# Teensylu-1_1.net
KiCad netlist of a schematic drawn in EAGLE
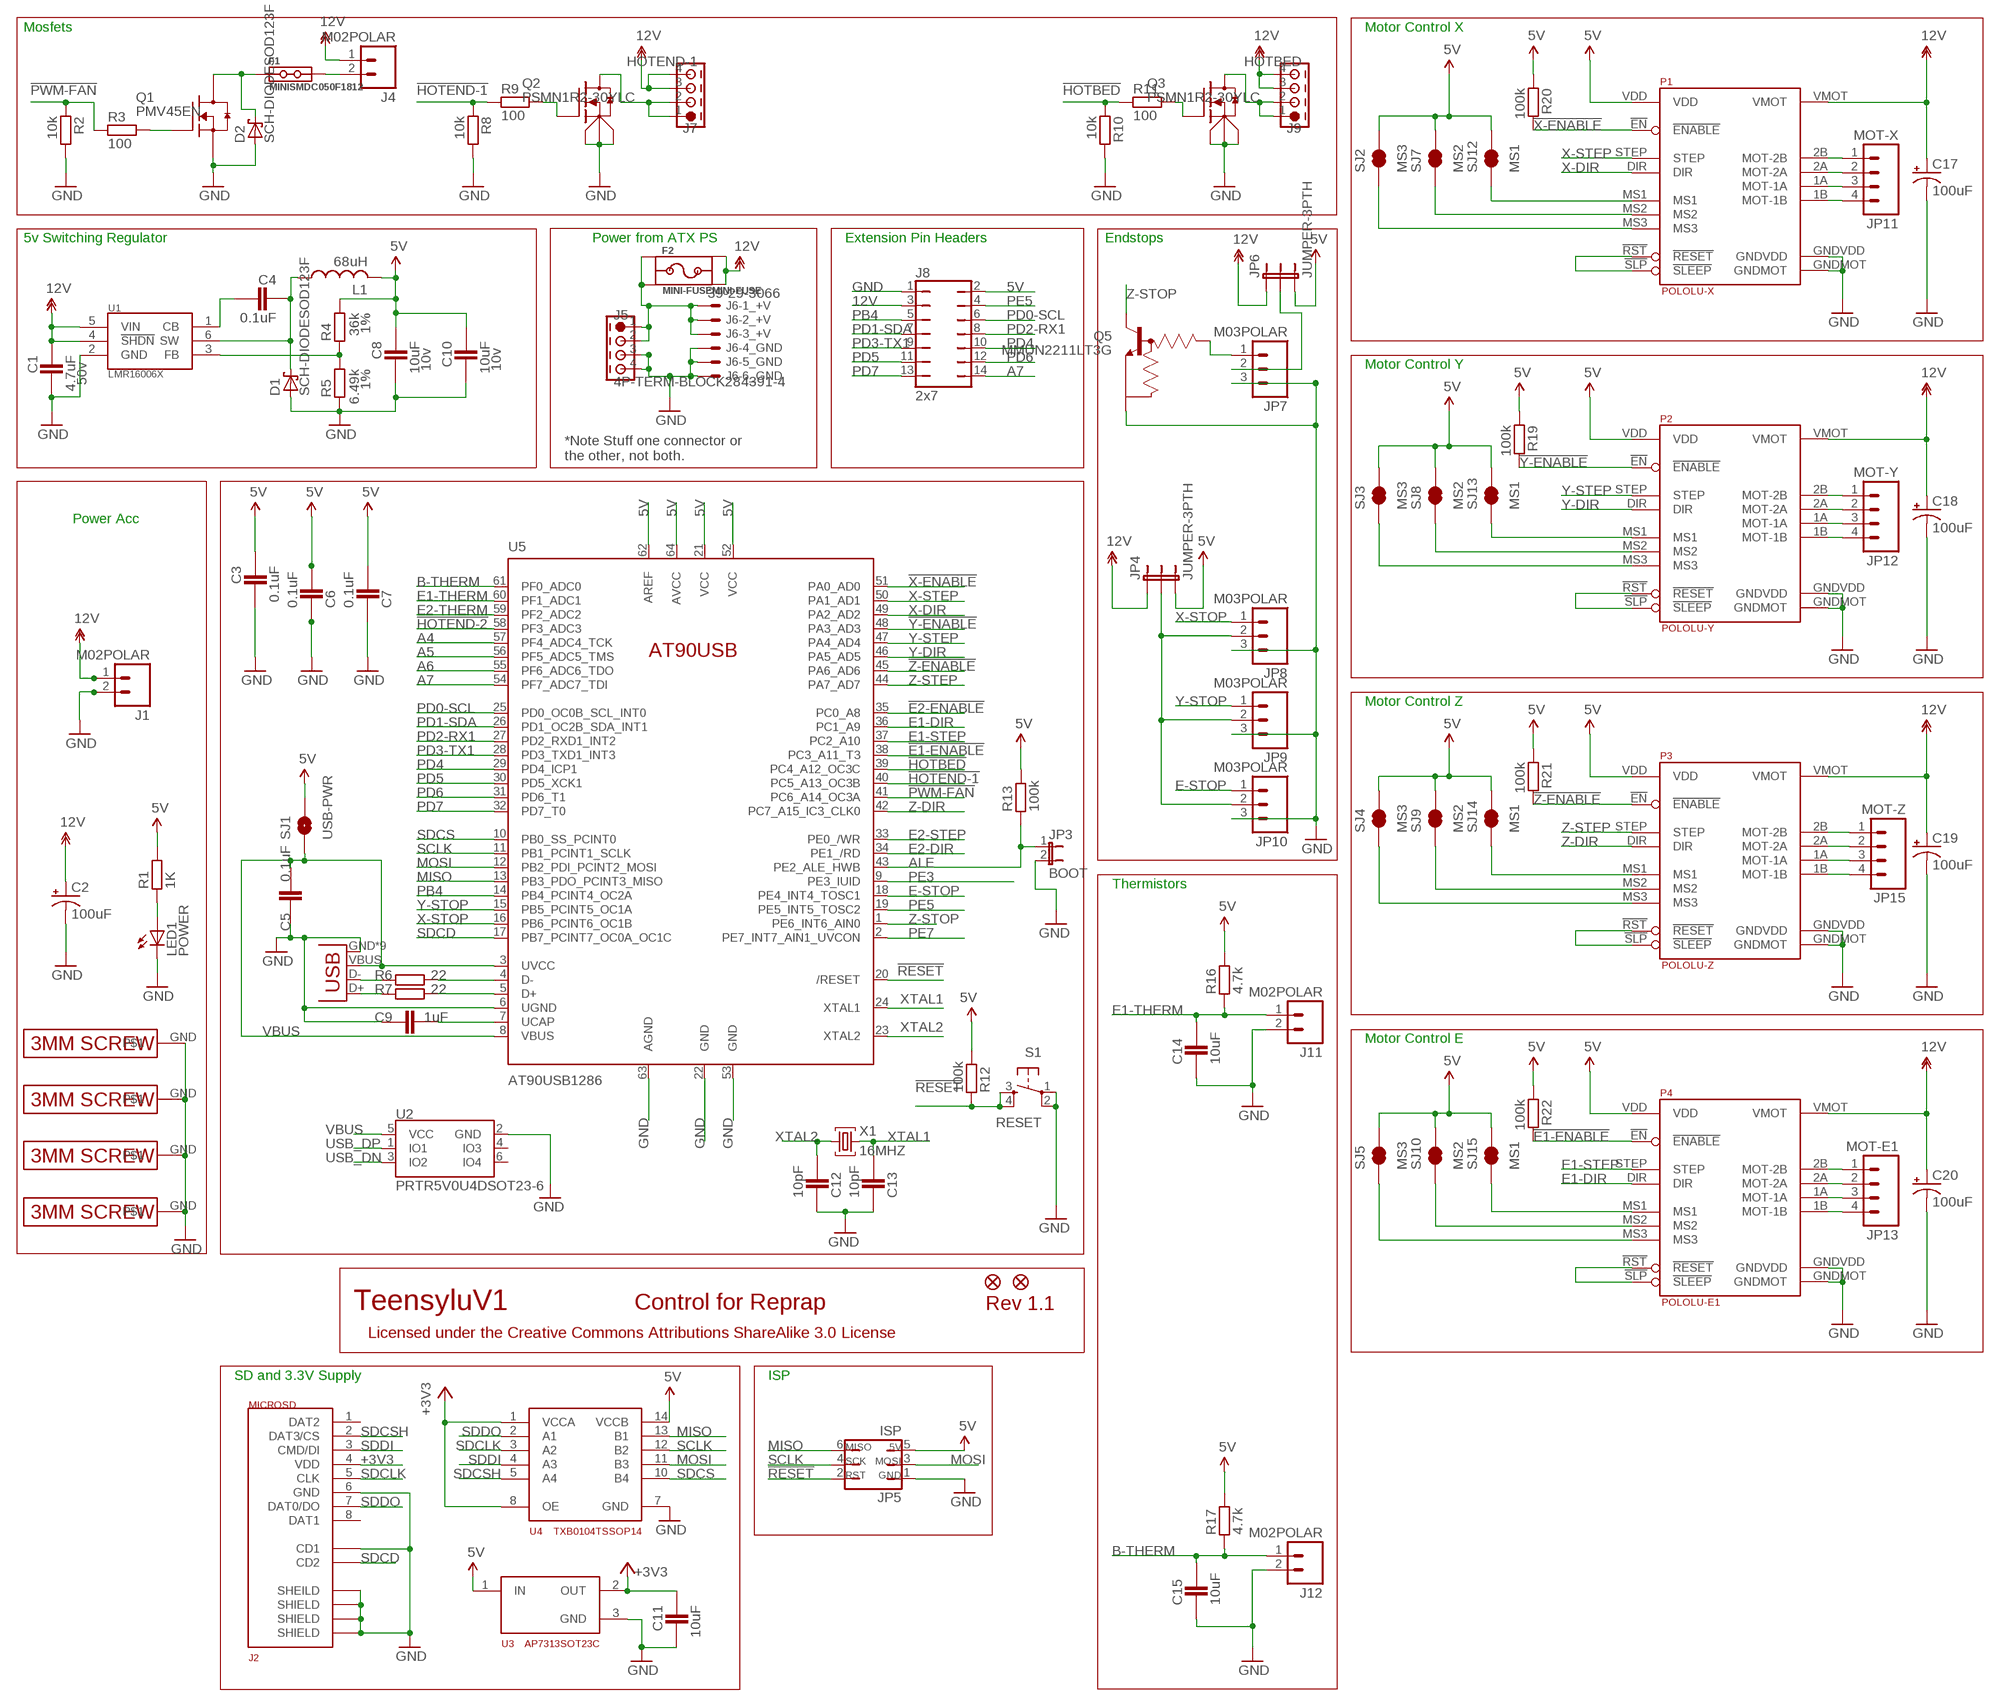
[diagram p0: schematic, sheet 1]

(export (version "E")
  (design (tool "Eeschema 10.0.6"))
  (components
    (comp (ref "C1")
      (value "4.7uF")
      (footprint "eagle-import:CAPC3215X168N")
      (fields
        (field (name "MANUFACTURER") "Yaiyo Yuden")
        (field (name "MANUFACTURER_PART_NUMBER") "UMK316AB7475KL-T")
        (field (name "TOLERANCE") "10%")
        (field (name "VDC") "50v")
      )
      (libsource (lib "eagle-import") (part "CAPACITOR_1206"))
    )
    (comp (ref "C2")
      (value "100uF")
      (footprint "eagle-import:PANASONIC_D")
      (fields
        (field (name "MANUFACTURER") "Panasonic")
        (field (name "MANUFACTURER_PART_NUMBER") "EEE-FTH101XAP")
        (field (name "TOLERANCE") "20%")
      )
      (libsource (lib "eagle-import") (part "CPOL-USD"))
    )
    (comp (ref "C3")
      (value "0.1uF")
      (footprint "eagle-import:CAPC1608X92N")
      (fields
        (field (name "MANUFACTURER") "Murata")
        (field (name "MANUFACTURER_PART_NUMBER") "GRM188R71C104KA01D")
        (field (name "TOLERANCE") "10%")
      )
      (libsource (lib "eagle-import") (part "CAPACITOR_0603"))
    )
    (comp (ref "C4")
      (value "0.1uF")
      (footprint "eagle-import:CAPC1608X92N")
      (fields
        (field (name "MANUFACTURER") "Samsung")
        (field (name "MANUFACTURER_PART_NUMBER") "CL10B104KB8NNNC")
        (field (name "TOLERANCE") "10%")
      )
      (libsource (lib "eagle-import") (part "CAPACITOR_0603"))
    )
    (comp (ref "C5")
      (value "0.1uF")
      (footprint "eagle-import:CAPC1608X92N")
      (fields
        (field (name "MANUFACTURER") "Murata")
        (field (name "MANUFACTURER_PART_NUMBER") "GRM188R71C104KA01D")
        (field (name "TOLERANCE") "10%")
      )
      (libsource (lib "eagle-import") (part "CAPACITOR_0603"))
    )
    (comp (ref "C6")
      (value "0.1uF")
      (footprint "eagle-import:CAPC1608X92N")
      (fields
        (field (name "MANUFACTURER") "Murata")
        (field (name "MANUFACTURER_PART_NUMBER") "GRM188R71C104KA01D")
        (field (name "TOLERANCE") "10%")
      )
      (libsource (lib "eagle-import") (part "CAPACITOR_0603"))
    )
    (comp (ref "C7")
      (value "0.1uF")
      (footprint "eagle-import:CAPC1608X92N")
      (fields
        (field (name "MANUFACTURER") "Murata")
        (field (name "MANUFACTURER_PART_NUMBER") "GRM188R71C104KA01D")
        (field (name "TOLERANCE") "10%")
      )
      (libsource (lib "eagle-import") (part "CAPACITOR_0603"))
    )
    (comp (ref "C8")
      (value "10uF")
      (footprint "eagle-import:CAPC2012X145AN")
      (fields
        (field (name "MANUFACTURER") "Murata")
        (field (name "MANUFACTURER_PART_NUMBER") "GRM21BR71A106KE51L")
        (field (name "TOLERANCE") "10%")
        (field (name "VDC") "10v")
      )
      (libsource (lib "eagle-import") (part "CAPACITOR_0805"))
    )
    (comp (ref "C9")
      (value "1uF")
      (footprint "eagle-import:CAPC1608X92N")
      (fields
        (field (name "MANUFACTURER") "Samsung")
        (field (name "MANUFACTURER_PART_NUMBER") "CL10A105MO8NNNC")
        (field (name "TOLERANCE") "20%")
      )
      (libsource (lib "eagle-import") (part "CAPACITOR_0603"))
    )
    (comp (ref "C10")
      (value "10uF")
      (footprint "eagle-import:CAPC2012X145AN")
      (fields
        (field (name "MANUFACTURER") "Murata")
        (field (name "MANUFACTURER_PART_NUMBER") "GRM21BR71A106KE51L")
        (field (name "TOLERANCE") "10%")
        (field (name "VDC") "10v")
      )
      (libsource (lib "eagle-import") (part "CAPACITOR_0805"))
    )
    (comp (ref "C11")
      (value "10uF")
      (footprint "eagle-import:CAPC1608X92N")
      (fields
        (field (name "MANUFACTURER") "Murata")
        (field (name "MANUFACTURER_PART_NUMBER") "GRM188R61C106MA73D")
        (field (name "TOLERANCE") "20%")
      )
      (libsource (lib "eagle-import") (part "CAPACITOR_0603"))
    )
    (comp (ref "C12")
      (value "10pF")
      (footprint "eagle-import:CAPC1608X92N")
      (fields
        (field (name "MANUFACTURER") "Samsung")
        (field (name "MANUFACTURER_PART_NUMBER") "CL10C100JB8NCNC")
        (field (name "TOLERANCE") "5%")
      )
      (libsource (lib "eagle-import") (part "CAPACITOR_0603"))
    )
    (comp (ref "C13")
      (value "10pF")
      (footprint "eagle-import:CAPC1608X92N")
      (fields
        (field (name "MANUFACTURER") "Samsung")
        (field (name "MANUFACTURER_PART_NUMBER") "CL10C100JB8NCNC")
        (field (name "TOLERANCE") "5%")
      )
      (libsource (lib "eagle-import") (part "CAPACITOR_0603"))
    )
    (comp (ref "C14")
      (value "10uF")
      (footprint "eagle-import:CAPC1608X92N")
      (fields
        (field (name "MANUFACTURER") "Murata")
        (field (name "MANUFACTURER_PART_NUMBER") "GRM188R61C106MA73D")
        (field (name "TOLERANCE") "20%")
      )
      (libsource (lib "eagle-import") (part "CAPACITOR_0603"))
    )
    (comp (ref "C15")
      (value "10uF")
      (footprint "eagle-import:CAPC1608X92N")
      (fields
        (field (name "MANUFACTURER") "Murata")
        (field (name "MANUFACTURER_PART_NUMBER") "GRM188R61C106MA73D")
        (field (name "TOLERANCE") "20%")
      )
      (libsource (lib "eagle-import") (part "CAPACITOR_0603"))
    )
    (comp (ref "C17")
      (value "100uF")
      (footprint "eagle-import:PANASONIC_D")
      (fields
        (field (name "MANUFACTURER") "Panasonic")
        (field (name "MANUFACTURER_PART_NUMBER") "EEE-FTH101XAP")
        (field (name "TOLERANCE") "20%")
      )
      (libsource (lib "eagle-import") (part "CPOL-USD"))
    )
    (comp (ref "C18")
      (value "100uF")
      (footprint "eagle-import:PANASONIC_D")
      (fields
        (field (name "MANUFACTURER") "Panasonic")
        (field (name "MANUFACTURER_PART_NUMBER") "EEE-FTH101XAP")
        (field (name "TOLERANCE") "20%")
      )
      (libsource (lib "eagle-import") (part "CPOL-USD"))
    )
    (comp (ref "C19")
      (value "100uF")
      (footprint "eagle-import:PANASONIC_D")
      (fields
        (field (name "MANUFACTURER") "Panasonic")
        (field (name "MANUFACTURER_PART_NUMBER") "EEE-FTH101XAP")
        (field (name "TOLERANCE") "20%")
      )
      (libsource (lib "eagle-import") (part "CPOL-USD"))
    )
    (comp (ref "C20")
      (value "100uF")
      (footprint "eagle-import:PANASONIC_D")
      (fields
        (field (name "MANUFACTURER") "Panasonic")
        (field (name "MANUFACTURER_PART_NUMBER") "EEE-FTH101XAP")
        (field (name "TOLERANCE") "20%")
      )
      (libsource (lib "eagle-import") (part "CPOL-USD"))
    )
    (comp (ref "D1")
      (value "SCH-DIODESOD123F")
      (footprint "eagle-import:SOD123F")
      (fields
        (field (name "MANUFACTURER") "NXP Semiconductors")
        (field (name "MANUFACTURER_PART_NUMBER") "PMEG4010CEH,115")
        (field (name "CURRENT") "1A")
        (field (name "MANUFACTURER_1") "NXP Semiconductors")
        (field (name "MANUFACTURER_PART_NUMBER_1") "PMEG4010CEH,115")
        (field (name "REVERSE_VOLTAGE") "40V")
      )
      (libsource (lib "eagle-import") (part "SCH-DIODESOD123F"))
    )
    (comp (ref "D2")
      (value "SCH-DIODESOD123F")
      (footprint "eagle-import:SOD123F")
      (fields
        (field (name "MANUFACTURER") "NXP Semiconductors")
        (field (name "MANUFACTURER_PART_NUMBER") "PMEG4010CEH,115")
        (field (name "CURRENT") "1A")
        (field (name "MANUFACTURER_1") "NXP Semiconductors")
      )
      (libsource (lib "eagle-import") (part "SCH-DIODESOD123F"))
    )
    (comp (ref "F1")
      (value "MINISMDC050F1812")
      (footprint "eagle-import:MINISMDC")
      (fields
        (field (name "MANUFACTURER") "TE Connectivity")
        (field (name "MANUFACTURER_PART_NUMBER") "MINISMDC050F-2")
      )
      (libsource (lib "eagle-import") (part "MINISMDC050F1812"))
    )
    (comp (ref "F2")
      (value "MINI-FUSEMINI-FUSE")
      (footprint "eagle-import:MINI_FUSE")
      (fields (field (name "MANUFACTURER") "Keystone") (field (name "MANUFACTURER_PART_NUMBER") "3568"))
      (libsource (lib "eagle-import") (part "MINI-FUSEMINI-FUSE"))
    )
    (comp (ref "J1")
      (value "M02POLAR")
      (footprint "eagle-import:MOLEX-1X2")
      (description "CONN HEADER 2POS .100 VERT TIN")
      (fields (field (name "MANUFACTURER") "Molex") (field (name "MANUFACTURER_PART_NUMBER") "0022272021"))
      (libsource (lib "eagle-import") (part "M02POLAR"))
    )
    (comp (ref "J2")
      (value "MICROSD")
      (footprint "eagle-import:AMPHENOL-MICROSD")
      (description "CONN MICRO SD CARD PUSH-PULL R/A")
      (fields
        (field (name "MANUFACTURER") "Amphenol")
        (field (name "MANUFACTURER_PART_NUMBER") "114-00841-68")
      )
      (libsource (lib "eagle-import") (part "MICROSD"))
    )
    (comp (ref "J3")
      (value "USB-MICRO-PTH")
      (footprint "eagle-import:USB-MICROB-PTH")
      (fields (field (name "MANUFACTURER") "FCI") (field (name "MANUFACTURER_PART_NUMBER") "10118194-0001LF"))
      (libsource (lib "eagle-import") (part "USB-MICRO-PTH"))
    )
    (comp (ref "J4")
      (value "M02POLAR")
      (footprint "eagle-import:MOLEX-1X2")
      (description "CONN HEADER 2POS .100 VERT TIN")
      (fields (field (name "MANUFACTURER") "Molex") (field (name "MANUFACTURER_PART_NUMBER") "0022272021"))
      (libsource (lib "eagle-import") (part "M02POLAR"))
    )
    (comp (ref "J5")
      (value "4P-TERM-BLOCK284391-4")
      (footprint "eagle-import:284391-4")
      (fields
        (field (name "MANUFACTURER") "TE Connectivity")
        (field (name "MANUFACTURER_PART_NUMBER") "284391-4")
      )
      (libsource (lib "eagle-import") (part "4P-TERM-BLOCK284391-4"))
    )
    (comp (ref "J6")
      (value "39-29-3066")
      (footprint "eagle-import:39-29-3066")
      (fields (field (name "MANUFACTURER") "Molex") (field (name "MANUFACTURER_PART_NUMBER") "0039293066"))
      (libsource (lib "eagle-import") (part "39-29-3066"))
    )
    (comp (ref "J7")
      (value "HOTEND-1")
      (footprint "eagle-import:284391-4")
      (fields
        (field (name "MANUFACTURER") "TE Connectivity")
        (field (name "MANUFACTURER_PART_NUMBER") "284391-4")
      )
      (libsource (lib "eagle-import") (part "4P-TERM-BLOCK284391-4"))
    )
    (comp (ref "J8")
      (value "2x7")
      (footprint "eagle-import:JP7Q")
      (description "DIL VERTICAL PC TAIL PIN HEADER")
      (fields (field (name "MANUFACTURER") "Harwin") (field (name "MANUFACTURER_PART_NUMBER") "M20-9980746"))
      (libsource (lib "eagle-import") (part "JP7Q"))
    )
    (comp (ref "J9")
      (value "HOTBED")
      (footprint "eagle-import:284391-4")
      (fields
        (field (name "MANUFACTURER") "TE Connectivity")
        (field (name "MANUFACTURER_PART_NUMBER") "284391-4")
      )
      (libsource (lib "eagle-import") (part "4P-TERM-BLOCK284391-4"))
    )
    (comp (ref "J11")
      (value "M02POLAR")
      (footprint "eagle-import:MOLEX-1X2")
      (description "CONN HEADER 2POS .100 VERT TIN")
      (fields (field (name "MANUFACTURER") "Molex") (field (name "MANUFACTURER_PART_NUMBER") "0022272021"))
      (libsource (lib "eagle-import") (part "M02POLAR"))
    )
    (comp (ref "J12")
      (value "M02POLAR")
      (footprint "eagle-import:MOLEX-1X2")
      (description "CONN HEADER 2POS .100 VERT TIN")
      (fields (field (name "MANUFACTURER") "Molex") (field (name "MANUFACTURER_PART_NUMBER") "0022272021"))
      (libsource (lib "eagle-import") (part "M02POLAR"))
    )
    (comp (ref "JP1")
      (value "FIDUCIAL1X2.5")
      (footprint "eagle-import:FIDUCIAL-1X2.5")
      (libsource (lib "eagle-import") (part "FIDUCIAL1X2.5"))
    )
    (comp (ref "JP2")
      (value "FIDUCIAL1X2.5")
      (footprint "eagle-import:FIDUCIAL-1X2.5")
      (libsource (lib "eagle-import") (part "FIDUCIAL1X2.5"))
    )
    (comp (ref "JP3")
      (value "BOOT")
      (footprint "eagle-import:1X02")
      (description "SIL VERTICAL PC TAIL PIN HEADER")
      (fields (field (name "MANUFACTURER") "Harwin") (field (name "MANUFACTURER_PART_NUMBER") "M20-9990246"))
      (libsource (lib "eagle-import") (part "JUMPER-2PTH"))
    )
    (comp (ref "JP4")
      (value "JUMPER-3PTH")
      (footprint "eagle-import:1X03")
      (libsource (lib "eagle-import") (part "JUMPER-3PTH"))
    )
    (comp (ref "JP5")
      (value "ISP")
      (footprint "eagle-import:ISP")
      (libsource (lib "eagle-import") (part "PROGHEADER"))
    )
    (comp (ref "JP6")
      (value "JUMPER-3PTH")
      (footprint "eagle-import:1X03")
      (libsource (lib "eagle-import") (part "JUMPER-3PTH"))
    )
    (comp (ref "JP7")
      (value "M03POLAR")
      (footprint "eagle-import:MOLEX-1X3")
      (description "CONN HEADER 3POS .100 VERT TIN")
      (fields (field (name "MANUFACTURER") "Molex") (field (name "MANUFACTURER_PART_NUMBER") "0022272031"))
      (libsource (lib "eagle-import") (part "M03POLAR"))
    )
    (comp (ref "JP8")
      (value "M03POLAR")
      (footprint "eagle-import:MOLEX-1X3")
      (description "CONN HEADER 3POS .100 VERT TIN")
      (fields (field (name "MANUFACTURER") "Molex") (field (name "MANUFACTURER_PART_NUMBER") "0022272031"))
      (libsource (lib "eagle-import") (part "M03POLAR"))
    )
    (comp (ref "JP9")
      (value "M03POLAR")
      (footprint "eagle-import:MOLEX-1X3")
      (description "CONN HEADER 3POS .100 VERT TIN")
      (fields (field (name "MANUFACTURER") "Molex") (field (name "MANUFACTURER_PART_NUMBER") "0022272031"))
      (libsource (lib "eagle-import") (part "M03POLAR"))
    )
    (comp (ref "JP10")
      (value "M03POLAR")
      (footprint "eagle-import:MOLEX-1X3")
      (description "CONN HEADER 3POS .100 VERT TIN")
      (fields (field (name "MANUFACTURER") "Molex") (field (name "MANUFACTURER_PART_NUMBER") "0022272031"))
      (libsource (lib "eagle-import") (part "M03POLAR"))
    )
    (comp (ref "JP11")
      (value "MOT-X")
      (footprint "eagle-import:MOLEX-1X4")
      (fields (field (name "MANUFACTURER") "Molex") (field (name "MANUFACTURER_PART_NUMBER") "0022272041"))
      (libsource (lib "eagle-import") (part "M04POLAR"))
    )
    (comp (ref "JP12")
      (value "MOT-Y")
      (footprint "eagle-import:MOLEX-1X4")
      (fields (field (name "MANUFACTURER") "Molex") (field (name "MANUFACTURER_PART_NUMBER") "0022272041"))
      (libsource (lib "eagle-import") (part "M04POLAR"))
    )
    (comp (ref "JP13")
      (value "MOT-E1")
      (footprint "eagle-import:MOLEX-1X4")
      (fields (field (name "MANUFACTURER") "Molex") (field (name "MANUFACTURER_PART_NUMBER") "0022272041"))
      (libsource (lib "eagle-import") (part "M04POLAR"))
    )
    (comp (ref "JP15")
      (value "MOT-Z")
      (footprint "eagle-import:MOLEX-1X4")
      (fields (field (name "MANUFACTURER") "Molex") (field (name "MANUFACTURER_PART_NUMBER") "0022272041"))
      (libsource (lib "eagle-import") (part "M04POLAR"))
    )
    (comp (ref "L1")
      (value "68uH")
      (footprint "eagle-import:SRN6045")
      (fields
        (field (name "MANUFACTURER") "Bourns")
        (field (name "MANUFACTURER_PART_NUMBER") "SRN6045-680M")
        (field (name "MANUFACTURER_1") "Bourns")
        (field (name "MANUFACTURER_PART_NUMBER_1") "SRN6045-680M")
      )
      (libsource (lib "eagle-import") (part "INDUCTORSRN6045"))
    )
    (comp (ref "LED1")
      (value "POWER")
      (footprint "eagle-import:CHIPLED_0805")
      (fields
        (field (name "MANUFACTURER") "Kingbright")
        (field (name "MANUFACTURER_PART_NUMBER") "APT2012SGC")
      )
      (libsource (lib "eagle-import") (part "LEDCHIPLED_0805"))
    )
    (comp (ref "P1")
      (value "POLOLU-X")
      (footprint "eagle-import:POLOLU-STEPPER-PTH")
      (libsource (lib "eagle-import") (part "POLOLU-ALLEGRO"))
    )
    (comp (ref "P2")
      (value "POLOLU-Y")
      (footprint "eagle-import:POLOLU-STEPPER-PTH")
      (libsource (lib "eagle-import") (part "POLOLU-ALLEGRO"))
    )
    (comp (ref "P3")
      (value "POLOLU-Z")
      (footprint "eagle-import:POLOLU-STEPPER-PTH")
      (libsource (lib "eagle-import") (part "POLOLU-ALLEGRO"))
    )
    (comp (ref "P4")
      (value "POLOLU-E1")
      (footprint "eagle-import:POLOLU-STEPPER-PTH")
      (libsource (lib "eagle-import") (part "POLOLU-ALLEGRO"))
    )
    (comp (ref "Q1")
      (value "PMV45EN")
      (footprint "eagle-import:SOT23C")
      (fields
        (field (name "MANUFACTURER") "International Rectifier")
        (field (name "MANUFACTURER_PART_NUMBER") "IRLML2060TRPBF")
        (field (name "VOLTAGE") "60V")
      )
      (libsource (lib "eagle-import") (part "MOSFET-NCH_SOT-23"))
    )
    (comp (ref "Q2")
      (value "PSMN1R2-30YLC")
      (footprint "eagle-import:LFPACK-POWERPAK-SO8")
      (fields
        (field (name "MANUFACTURER") "NXP Semiconductors")
        (field (name "MANUFACTURER_PART_NUMBER") "PSMN1R2-30YLC,115")
        (field (name "VOLTAGE") "30V")
      )
      (libsource (lib "eagle-import") (part "PSMN1R2-30YLCPOWERPACK-S08"))
    )
    (comp (ref "Q3")
      (value "PSMN1R2-30YLC")
      (footprint "eagle-import:LFPACK-POWERPAK-SO8")
      (fields
        (field (name "MANUFACTURER") "NXP Semiconductors")
        (field (name "MANUFACTURER_PART_NUMBER") "PSMN1R2-30YLC,115")
        (field (name "VOLTAGE") "30V")
      )
      (libsource (lib "eagle-import") (part "PSMN1R2-30YLCPOWERPACK-S08"))
    )
    (comp (ref "Q5")
      (value "MMUN2211LT3G")
      (footprint "eagle-import:SOT23C")
      (description "TRANS PREBIAS NPN 246MW SOT23-3")
      (fields (field (name "MANUFACTURER") "ON Semiconductor"))
      (libsource (lib "eagle-import") (part "TRANSISTOR_NPN_BIASSOT23C"))
    )
    (comp (ref "R1")
      (value "1K")
      (footprint "eagle-import:RESC1608X55N")
      (libsource (lib "eagle-import") (part "RESISTOR_0603"))
    )
    (comp (ref "R2")
      (value "10k")
      (footprint "eagle-import:RESC1608X55N")
      (libsource (lib "eagle-import") (part "RESISTOR_0603"))
    )
    (comp (ref "R3")
      (value "100")
      (footprint "eagle-import:RESC1608X55N")
      (libsource (lib "eagle-import") (part "RESISTOR_0603"))
    )
    (comp (ref "R4")
      (value "36k")
      (footprint "eagle-import:RESC1608X55N")
      (fields (field (name "TOLERANCE") "1%"))
      (libsource (lib "eagle-import") (part "RESISTOR_0603"))
    )
    (comp (ref "R5")
      (value "6.49k")
      (footprint "eagle-import:RESC1608X55N")
      (fields (field (name "TOLERANCE") "1%"))
      (libsource (lib "eagle-import") (part "RESISTOR_0603"))
    )
    (comp (ref "R6")
      (value "22")
      (footprint "eagle-import:RESC1608X55N")
      (libsource (lib "eagle-import") (part "RESISTOR_0603"))
    )
    (comp (ref "R7")
      (value "22")
      (footprint "eagle-import:RESC1608X55N")
      (libsource (lib "eagle-import") (part "RESISTOR_0603"))
    )
    (comp (ref "R8")
      (value "10k")
      (footprint "eagle-import:RESC1608X55N")
      (libsource (lib "eagle-import") (part "RESISTOR_0603"))
    )
    (comp (ref "R9")
      (value "100")
      (footprint "eagle-import:RESC1608X55N")
      (libsource (lib "eagle-import") (part "RESISTOR_0603"))
    )
    (comp (ref "R10")
      (value "10k")
      (footprint "eagle-import:RESC1608X55N")
      (libsource (lib "eagle-import") (part "RESISTOR_0603"))
    )
    (comp (ref "R11")
      (value "100")
      (footprint "eagle-import:RESC1608X55N")
      (libsource (lib "eagle-import") (part "RESISTOR_0603"))
    )
    (comp (ref "R12")
      (value "100k")
      (footprint "eagle-import:RESC1608X55N")
      (libsource (lib "eagle-import") (part "RESISTOR_0603"))
    )
    (comp (ref "R13")
      (value "100k")
      (footprint "eagle-import:RESC1608X55N")
      (libsource (lib "eagle-import") (part "RESISTOR_0603"))
    )
    (comp (ref "R16")
      (value "4.7k")
      (footprint "eagle-import:RESC1608X55N")
      (libsource (lib "eagle-import") (part "RESISTOR_0603"))
    )
    (comp (ref "R17")
      (value "4.7k")
      (footprint "eagle-import:RESC1608X55N")
      (libsource (lib "eagle-import") (part "RESISTOR_0603"))
    )
    (comp (ref "R19")
      (value "100k")
      (footprint "eagle-import:RESC1608X55N")
      (libsource (lib "eagle-import") (part "RESISTOR_0603"))
    )
    (comp (ref "R20")
      (value "100k")
      (footprint "eagle-import:RESC1608X55N")
      (libsource (lib "eagle-import") (part "RESISTOR_0603"))
    )
    (comp (ref "R21")
      (value "100k")
      (footprint "eagle-import:RESC1608X55N")
      (libsource (lib "eagle-import") (part "RESISTOR_0603"))
    )
    (comp (ref "R22")
      (value "100k")
      (footprint "eagle-import:RESC1608X55N")
      (libsource (lib "eagle-import") (part "RESISTOR_0603"))
    )
    (comp (ref "S1")
      (value "RESET")
      (footprint "eagle-import:TACTILE_SWITCH_SMD")
      (fields (field (name "MANUFACTURER") "Bourns") (field (name "MANUFACTURER_PART_NUMBER") "7914J-1-000E"))
      (libsource (lib "eagle-import") (part "TAC_SWITCHSMD"))
    )
    (comp (ref "SCREW1")
      (value "3MM-SCREW")
      (footprint "eagle-import:PLATEDSCREW")
      (libsource (lib "eagle-import") (part "3MM-SCREW"))
    )
    (comp (ref "SCREW2")
      (value "3MM-SCREW")
      (footprint "eagle-import:PLATEDSCREW")
      (libsource (lib "eagle-import") (part "3MM-SCREW"))
    )
    (comp (ref "SCREW3")
      (value "3MM-SCREW")
      (footprint "eagle-import:PLATEDSCREW")
      (libsource (lib "eagle-import") (part "3MM-SCREW"))
    )
    (comp (ref "SCREW4")
      (value "3MM-SCREW")
      (footprint "eagle-import:PLATEDSCREW")
      (libsource (lib "eagle-import") (part "3MM-SCREW"))
    )
    (comp (ref "SJ1")
      (value "USB-PWR")
      (footprint "eagle-import:SJ_2S-NO")
      (libsource (lib "eagle-import") (part "SOLDERJUMPERNO"))
    )
    (comp (ref "SJ2")
      (value "MS3")
      (footprint "eagle-import:SJ_2S-TRACE")
      (libsource (lib "eagle-import") (part "SOLDERJUMPER-NCSJ-TRACE"))
    )
    (comp (ref "SJ3")
      (value "MS3")
      (footprint "eagle-import:SJ_2S-TRACE")
      (libsource (lib "eagle-import") (part "SOLDERJUMPER-NCSJ-TRACE"))
    )
    (comp (ref "SJ4")
      (value "MS3")
      (footprint "eagle-import:SJ_2S-TRACE")
      (libsource (lib "eagle-import") (part "SOLDERJUMPER-NCSJ-TRACE"))
    )
    (comp (ref "SJ5")
      (value "MS3")
      (footprint "eagle-import:SJ_2S-TRACE")
      (libsource (lib "eagle-import") (part "SOLDERJUMPER-NCSJ-TRACE"))
    )
    (comp (ref "SJ7")
      (value "MS2")
      (footprint "eagle-import:SJ_2S-TRACE")
      (libsource (lib "eagle-import") (part "SOLDERJUMPER-NCSJ-TRACE"))
    )
    (comp (ref "SJ8")
      (value "MS2")
      (footprint "eagle-import:SJ_2S-TRACE")
      (libsource (lib "eagle-import") (part "SOLDERJUMPER-NCSJ-TRACE"))
    )
    (comp (ref "SJ9")
      (value "MS2")
      (footprint "eagle-import:SJ_2S-TRACE")
      (libsource (lib "eagle-import") (part "SOLDERJUMPER-NCSJ-TRACE"))
    )
    (comp (ref "SJ10")
      (value "MS2")
      (footprint "eagle-import:SJ_2S-TRACE")
      (libsource (lib "eagle-import") (part "SOLDERJUMPER-NCSJ-TRACE"))
    )
    (comp (ref "SJ12")
      (value "MS1")
      (footprint "eagle-import:SJ_2S-TRACE")
      (libsource (lib "eagle-import") (part "SOLDERJUMPER-NCSJ-TRACE"))
    )
    (comp (ref "SJ13")
      (value "MS1")
      (footprint "eagle-import:SJ_2S-TRACE")
      (libsource (lib "eagle-import") (part "SOLDERJUMPER-NCSJ-TRACE"))
    )
    (comp (ref "SJ14")
      (value "MS1")
      (footprint "eagle-import:SJ_2S-TRACE")
      (libsource (lib "eagle-import") (part "SOLDERJUMPER-NCSJ-TRACE"))
    )
    (comp (ref "SJ15")
      (value "MS1")
      (footprint "eagle-import:SJ_2S-TRACE")
      (libsource (lib "eagle-import") (part "SOLDERJUMPER-NCSJ-TRACE"))
    )
    (comp (ref "U1")
      (value "LMR16006X")
      (footprint "eagle-import:TSOT6")
      (fields
        (field (name "MANUFACTURER") "Texas Instruments")
        (field (name "MANUFACTURER_PART_NUMBER") "LMR16006XDDCT")
      )
      (libsource (lib "eagle-import") (part "LMR16006X"))
    )
    (comp (ref "U2")
      (value "PRTR5V0U4DSOT23-6")
      (footprint "eagle-import:SOT23-6")
      (fields
        (field (name "MANUFACTURER") "NXP Semiconductors")
        (field (name "MANUFACTURER_PART_NUMBER") "PRTR5V0U4D,125")
      )
      (libsource (lib "eagle-import") (part "PRTR5V0U4DSOT23-6"))
    )
    (comp (ref "U3")
      (value "AP7313SOT23C")
      (footprint "eagle-import:SOT23C")
      (description "IC REG LDO 3.3V 0.15A SOT23-3")
      (fields
        (field (name "MANUFACTURER") "Diodes Incorporated")
        (field (name "MANUFACTURER_PART_NUMBER") "AP7313-33SAG-7")
      )
      (libsource (lib "eagle-import") (part "AP7313SOT23C"))
    )
    (comp (ref "U4")
      (value "TXB0104TSSOP14")
      (footprint "eagle-import:TSSOP14")
      (description "IC VOLT-LEVEL TRANSLATOR 14TSSOP")
      (fields
        (field (name "MANUFACTURER") "Texas Instruments")
        (field (name "MANUFACTURER_PART_NUMBER") "TXB0104PWR")
      )
      (libsource (lib "eagle-import") (part "TXB0104TSSOP14"))
    )
    (comp (ref "U5")
      (value "AT90USB1286")
      (footprint "eagle-import:TQFP64-2")
      (fields (field (name "MANUFACTURER") "Atmel"))
      (libsource (lib "eagle-import") (part "AT90USB"))
    )
    (comp (ref "X1")
      (value "16MHZ")
      (footprint "eagle-import:NDK-XTAL")
      (fields
        (field (name "MANUFACTURER") "NDK")
        (field (name "MANUFACTURER_PART_NUMBER") "NX5032GA-16.000000MHZ-LN-CD-1")
      )
      (libsource (lib "eagle-import") (part "XTAL"))
    )
  )
  (nets
    (net (code "1") (name "+3V3") (class "Default")
      (node (ref "C11") (pin "1") (pinfunction "1_1") (pintype "passive"))
      (node (ref "J2") (pin "4") (pinfunction "VDD_4") (pintype "power_in"))
      (node (ref "U3") (pin "2") (pinfunction "OUT_2") (pintype "power_in"))
      (node (ref "U4") (pin "1") (pinfunction "VCCA_1") (pintype "power_in"))
      (node (ref "U4") (pin "8") (pinfunction "OE_8") (pintype "input"))
    )
    (net (code "2") (name "/A4") (class "Default")
      (node (ref "U5") (pin "57") (pinfunction "PF4_ADC4_TCK_57") (pintype "bidirectional"))
    )
    (net (code "3") (name "/A5") (class "Default")
      (node (ref "U5") (pin "56") (pinfunction "PF5_ADC5_TMS_56") (pintype "bidirectional"))
    )
    (net (code "4") (name "/A6") (class "Default")
      (node (ref "U5") (pin "55") (pinfunction "PF6_ADC6_TDO_55") (pintype "bidirectional"))
    )
    (net (code "5") (name "/A7") (class "Default")
      (node (ref "J8") (pin "14") (pinfunction "14_14") (pintype "passive"))
      (node (ref "U5") (pin "54") (pinfunction "PF7_ADC7_TDI_54") (pintype "bidirectional"))
    )
    (net (code "6") (name "/ALE") (class "Default")
      (node (ref "JP3") (pin "1") (pinfunction "1_1") (pintype "passive"))
      (node (ref "R13") (pin "1") (pinfunction "1_1") (pintype "passive"))
      (node (ref "U5") (pin "43") (pinfunction "PE2_ALE_HWB_43") (pintype "bidirectional"))
    )
    (net (code "7") (name "/B-THERM") (class "Default")
      (node (ref "C15") (pin "2") (pinfunction "2_2") (pintype "passive"))
      (node (ref "J12") (pin "1") (pinfunction "1_1") (pintype "passive"))
      (node (ref "R17") (pin "1") (pinfunction "1_1") (pintype "passive"))
      (node (ref "U5") (pin "61") (pinfunction "PF0_ADC0_61") (pintype "bidirectional"))
    )
    (net (code "8") (name "/E-STOP") (class "Default")
      (node (ref "JP10") (pin "1") (pinfunction "1_1") (pintype "passive"))
      (node (ref "U5") (pin "18") (pinfunction "PE4_INT4_TOSC1_18") (pintype "bidirectional"))
    )
    (net (code "9") (name "/E1-DIR") (class "Default")
      (node (ref "P4") (pin "DIR") (pinfunction "DIR_DIR") (pintype "bidirectional"))
      (node (ref "U5") (pin "36") (pinfunction "PC1_A9_36") (pintype "bidirectional"))
    )
    (net (code "10") (name "/E1-STEP") (class "Default")
      (node (ref "P4") (pin "STEP") (pinfunction "STEP_STEP") (pintype "bidirectional"))
      (node (ref "U5") (pin "37") (pinfunction "PC2_A10_37") (pintype "bidirectional"))
    )
    (net (code "11") (name "/E1-THERM") (class "Default")
      (node (ref "C14") (pin "2") (pinfunction "2_2") (pintype "passive"))
      (node (ref "J11") (pin "1") (pinfunction "1_1") (pintype "passive"))
      (node (ref "R16") (pin "1") (pinfunction "1_1") (pintype "passive"))
      (node (ref "U5") (pin "60") (pinfunction "PF1_ADC1_60") (pintype "bidirectional"))
    )
    (net (code "12") (name "/E2-DIR") (class "Default")
      (node (ref "U5") (pin "34") (pinfunction "PE1_/RD_34") (pintype "bidirectional"))
    )
    (net (code "13") (name "/E2-STEP") (class "Default")
      (node (ref "U5") (pin "33") (pinfunction "PE0_/WR_33") (pintype "bidirectional"))
    )
    (net (code "14") (name "/E2-THERM") (class "Default")
      (node (ref "U5") (pin "59") (pinfunction "PF2_ADC2_59") (pintype "bidirectional"))
    )
    (net (code "15") (name "/MISO") (class "Default")
      (node (ref "JP5") (pin "6") (pinfunction "6_6") (pintype "passive"))
      (node (ref "U4") (pin "13") (pinfunction "B1_13") (pintype "bidirectional"))
      (node (ref "U5") (pin "13") (pinfunction "PB3_PDO_PCINT3_MISO_13") (pintype "bidirectional"))
    )
    (net (code "16") (name "/MOSI") (class "Default")
      (node (ref "JP5") (pin "3") (pinfunction "3_3") (pintype "passive"))
      (node (ref "U4") (pin "11") (pinfunction "B3_11") (pintype "bidirectional"))
      (node (ref "U5") (pin "12") (pinfunction "PB2_PDI_PCINT2_MOSI_12") (pintype "bidirectional"))
    )
    (net (code "17") (name "/PB4") (class "Default")
      (node (ref "J8") (pin "5") (pinfunction "5_5") (pintype "passive"))
      (node (ref "U5") (pin "14") (pinfunction "PB4_PCINT4_OC2A_14") (pintype "bidirectional"))
    )
    (net (code "18") (name "/PD0-SCL") (class "Default")
      (node (ref "J8") (pin "6") (pinfunction "6_6") (pintype "passive"))
      (node (ref "U5") (pin "25") (pinfunction "PD0_OC0B_SCL_INT0_25") (pintype "bidirectional"))
    )
    (net (code "19") (name "/PD1-SDA") (class "Default")
      (node (ref "J8") (pin "7") (pinfunction "7_7") (pintype "passive"))
      (node (ref "U5") (pin "26") (pinfunction "PD1_OC2B_SDA_INT1_26") (pintype "bidirectional"))
    )
    (net (code "20") (name "/PD2-RX1") (class "Default")
      (node (ref "J8") (pin "8") (pinfunction "8_8") (pintype "passive"))
      (node (ref "U5") (pin "27") (pinfunction "PD2_RXD1_INT2_27") (pintype "bidirectional"))
    )
    (net (code "21") (name "/PD3-TX1") (class "Default")
      (node (ref "J8") (pin "9") (pinfunction "9_9") (pintype "passive"))
      (node (ref "U5") (pin "28") (pinfunction "PD3_TXD1_INT3_28") (pintype "bidirectional"))
    )
    (net (code "22") (name "/PD4") (class "Default")
      (node (ref "J8") (pin "10") (pinfunction "10_10") (pintype "passive"))
      (node (ref "U5") (pin "29") (pinfunction "PD4_ICP1_29") (pintype "bidirectional"))
    )
    (net (code "23") (name "/PD5") (class "Default")
      (node (ref "J8") (pin "11") (pinfunction "11_11") (pintype "passive"))
      (node (ref "U5") (pin "30") (pinfunction "PD5_XCK1_30") (pintype "bidirectional"))
    )
    (net (code "24") (name "/PD6") (class "Default")
      (node (ref "J8") (pin "12") (pinfunction "12_12") (pintype "passive"))
      (node (ref "U5") (pin "31") (pinfunction "PD6_T1_31") (pintype "bidirectional"))
    )
    (net (code "25") (name "/PD7") (class "Default")
      (node (ref "J8") (pin "13") (pinfunction "13_13") (pintype "passive"))
      (node (ref "U5") (pin "32") (pinfunction "PD7_T0_32") (pintype "bidirectional"))
    )
    (net (code "26") (name "/PE3") (class "Default")
      (node (ref "U5") (pin "9") (pinfunction "PE3_IUID_9") (pintype "bidirectional"))
    )
    (net (code "27") (name "/PE5") (class "Default")
      (node (ref "J8") (pin "4") (pinfunction "4_4") (pintype "passive"))
      (node (ref "U5") (pin "19") (pinfunction "PE5_INT5_TOSC2_19") (pintype "bidirectional"))
    )
    (net (code "28") (name "/PE7") (class "Default")
      (node (ref "U5") (pin "2") (pinfunction "PE7_INT7_AIN1_UVCON_2") (pintype "bidirectional"))
    )
    (net (code "29") (name "/SCLK") (class "Default")
      (node (ref "JP5") (pin "4") (pinfunction "4_4") (pintype "passive"))
      (node (ref "U4") (pin "12") (pinfunction "B2_12") (pintype "bidirectional"))
      (node (ref "U5") (pin "11") (pinfunction "PB1_PCINT1_SCLK_11") (pintype "bidirectional"))
    )
    (net (code "30") (name "/SDCD") (class "Default")
      (node (ref "J2") (pin "CD2") (pinfunction "CD2_CD2") (pintype "bidirectional"))
      (node (ref "U5") (pin "17") (pinfunction "PB7_PCINT7_OC0A_OC1C_17") (pintype "bidirectional"))
    )
    (net (code "31") (name "/SDCLK") (class "Default")
      (node (ref "J2") (pin "5") (pinfunction "CLK_5") (pintype "input"))
      (node (ref "U4") (pin "3") (pinfunction "A2_3") (pintype "bidirectional"))
    )
    (net (code "32") (name "/SDCS") (class "Default")
      (node (ref "U4") (pin "10") (pinfunction "B4_10") (pintype "bidirectional"))
      (node (ref "U5") (pin "10") (pinfunction "PB0_SS_PCINT0_10") (pintype "bidirectional"))
    )
    (net (code "33") (name "/SDCSH") (class "Default")
      (node (ref "J2") (pin "2") (pinfunction "DAT3/CS_2") (pintype "bidirectional"))
      (node (ref "U4") (pin "5") (pinfunction "A4_5") (pintype "bidirectional"))
    )
    (net (code "34") (name "/SDDI") (class "Default")
      (node (ref "J2") (pin "3") (pinfunction "CMD/DI_3") (pintype "input"))
      (node (ref "U4") (pin "4") (pinfunction "A3_4") (pintype "bidirectional"))
    )
    (net (code "35") (name "/SDDO") (class "Default")
      (node (ref "J2") (pin "7") (pinfunction "DAT0/DO_7") (pintype "bidirectional"))
      (node (ref "U4") (pin "2") (pinfunction "A1_2") (pintype "bidirectional"))
    )
    (net (code "36") (name "/USB_DN") (class "Default")
      (node (ref "J3") (pin "D-") (pinfunction "D-_D-") (pintype "bidirectional"))
      (node (ref "R6") (pin "1") (pinfunction "1_1") (pintype "passive"))
      (node (ref "U2") (pin "3") (pinfunction "IO2_3") (pintype "bidirectional"))
    )
    (net (code "37") (name "/USB_DP") (class "Default")
      (node (ref "J3") (pin "D+") (pinfunction "D+_D+") (pintype "bidirectional"))
      (node (ref "R7") (pin "1") (pinfunction "1_1") (pintype "passive"))
      (node (ref "U2") (pin "1") (pinfunction "IO1_1") (pintype "bidirectional"))
    )
    (net (code "38") (name "/VBUS") (class "Default")
      (node (ref "C5") (pin "2") (pinfunction "2_2") (pintype "passive"))
      (node (ref "J3") (pin "VBUS") (pinfunction "VBUS_VBUS") (pintype "bidirectional"))
      (node (ref "SJ1") (pin "1") (pinfunction "1_1") (pintype "passive"))
      (node (ref "U2") (pin "5") (pinfunction "VCC_5") (pintype "power_in"))
      (node (ref "U5") (pin "3") (pinfunction "UVCC_3") (pintype "power_in"))
      (node (ref "U5") (pin "8") (pinfunction "VBUS_8") (pintype "bidirectional"))
    )
    (net (code "39") (name "/X-DIR") (class "Default")
      (node (ref "P1") (pin "DIR") (pinfunction "DIR_DIR") (pintype "bidirectional"))
      (node (ref "U5") (pin "49") (pinfunction "PA2_AD2_49") (pintype "bidirectional"))
    )
    (net (code "40") (name "/X-STEP") (class "Default")
      (node (ref "P1") (pin "STEP") (pinfunction "STEP_STEP") (pintype "bidirectional"))
      (node (ref "U5") (pin "50") (pinfunction "PA1_AD1_50") (pintype "bidirectional"))
    )
    (net (code "41") (name "/X-STOP") (class "Default")
      (node (ref "JP8") (pin "1") (pinfunction "1_1") (pintype "passive"))
      (node (ref "U5") (pin "16") (pinfunction "PB6_PCINT6_OC1B_16") (pintype "bidirectional"))
    )
    (net (code "42") (name "/XTAL1") (class "Default")
      (node (ref "C13") (pin "2") (pinfunction "2_2") (pintype "passive"))
      (node (ref "U5") (pin "24") (pinfunction "XTAL1_24") (pintype "passive"))
      (node (ref "X1") (pin "P$2") (pinfunction "2_P$2") (pintype "passive"))
    )
    (net (code "43") (name "/XTAL2") (class "Default")
      (node (ref "C12") (pin "2") (pinfunction "2_2") (pintype "passive"))
      (node (ref "U5") (pin "23") (pinfunction "XTAL2_23") (pintype "passive"))
      (node (ref "X1") (pin "P$1") (pinfunction "1_P$1") (pintype "passive"))
    )
    (net (code "44") (name "/Y-DIR") (class "Default")
      (node (ref "P2") (pin "DIR") (pinfunction "DIR_DIR") (pintype "bidirectional"))
      (node (ref "U5") (pin "46") (pinfunction "PA5_AD5_46") (pintype "bidirectional"))
    )
    (net (code "45") (name "/Y-STEP") (class "Default")
      (node (ref "P2") (pin "STEP") (pinfunction "STEP_STEP") (pintype "bidirectional"))
      (node (ref "U5") (pin "47") (pinfunction "PA4_AD4_47") (pintype "bidirectional"))
    )
    (net (code "46") (name "/Y-STOP") (class "Default")
      (node (ref "JP9") (pin "1") (pinfunction "1_1") (pintype "passive"))
      (node (ref "U5") (pin "15") (pinfunction "PB5_PCINT5_OC1A_15") (pintype "bidirectional"))
    )
    (net (code "47") (name "/Z-DIR") (class "Default")
      (node (ref "P3") (pin "DIR") (pinfunction "DIR_DIR") (pintype "bidirectional"))
      (node (ref "U5") (pin "42") (pinfunction "PC7_A15_IC3_CLK0_42") (pintype "bidirectional"))
    )
    (net (code "48") (name "/Z-STEP") (class "Default")
      (node (ref "P3") (pin "STEP") (pinfunction "STEP_STEP") (pintype "bidirectional"))
      (node (ref "U5") (pin "44") (pinfunction "PA7_AD7_44") (pintype "bidirectional"))
    )
    (net (code "49") (name "/Z-STOP") (class "Default")
      (node (ref "Q5") (pin "3") (pinfunction "C_3") (pintype "passive"))
      (node (ref "U5") (pin "1") (pinfunction "PE6_INT6_AIN0_1") (pintype "bidirectional"))
    )
    (net (code "50") (name "/~{E1-ENABLE}") (class "Default")
      (node (ref "P4") (pin "!EN") (pinfunction "~{ENABLE}_!EN") (pintype "input"))
      (node (ref "R22") (pin "2") (pinfunction "2_2") (pintype "passive"))
      (node (ref "U5") (pin "38") (pinfunction "PC3_A11_T3_38") (pintype "bidirectional"))
    )
    (net (code "51") (name "/~{E2-ENABLE}") (class "Default")
      (node (ref "U5") (pin "35") (pinfunction "PC0_A8_35") (pintype "bidirectional"))
    )
    (net (code "52") (name "/~{HOTBED}") (class "Default")
      (node (ref "R10") (pin "1") (pinfunction "1_1") (pintype "passive"))
      (node (ref "R11") (pin "1") (pinfunction "1_1") (pintype "passive"))
      (node (ref "U5") (pin "39") (pinfunction "PC4_A12_OC3C_39") (pintype "bidirectional"))
    )
    (net (code "53") (name "/~{HOTEND-1}") (class "Default")
      (node (ref "R8") (pin "1") (pinfunction "1_1") (pintype "passive"))
      (node (ref "R9") (pin "1") (pinfunction "1_1") (pintype "passive"))
      (node (ref "U5") (pin "40") (pinfunction "PC5_A13_OC3B_40") (pintype "bidirectional"))
    )
    (net (code "54") (name "/~{HOTEND-2}") (class "Default")
      (node (ref "U5") (pin "58") (pinfunction "PF3_ADC3_58") (pintype "bidirectional"))
    )
    (net (code "55") (name "/~{PWM-FAN}") (class "Default")
      (node (ref "R2") (pin "1") (pinfunction "1_1") (pintype "passive"))
      (node (ref "R3") (pin "1") (pinfunction "1_1") (pintype "passive"))
      (node (ref "U5") (pin "41") (pinfunction "PC6_A14_OC3A_41") (pintype "bidirectional"))
    )
    (net (code "56") (name "/~{RESET}") (class "Default")
      (node (ref "JP5") (pin "2") (pinfunction "2_2") (pintype "passive"))
      (node (ref "R12") (pin "1") (pinfunction "1_1") (pintype "passive"))
      (node (ref "S1") (pin "3") (pinfunction "3_3") (pintype "passive"))
      (node (ref "S1") (pin "4") (pinfunction "4_4") (pintype "passive"))
      (node (ref "U5") (pin "20") (pinfunction "/RESET_20") (pintype "bidirectional"))
    )
    (net (code "57") (name "/~{X-ENABLE}") (class "Default")
      (node (ref "P1") (pin "!EN") (pinfunction "~{ENABLE}_!EN") (pintype "input"))
      (node (ref "R20") (pin "2") (pinfunction "2_2") (pintype "passive"))
      (node (ref "U5") (pin "51") (pinfunction "PA0_AD0_51") (pintype "bidirectional"))
    )
    (net (code "58") (name "/~{Y-ENABLE}") (class "Default")
      (node (ref "P2") (pin "!EN") (pinfunction "~{ENABLE}_!EN") (pintype "input"))
      (node (ref "R19") (pin "2") (pinfunction "2_2") (pintype "passive"))
      (node (ref "U5") (pin "48") (pinfunction "PA3_AD3_48") (pintype "bidirectional"))
    )
    (net (code "59") (name "/~{Z-ENABLE}") (class "Default")
      (node (ref "P3") (pin "!EN") (pinfunction "~{ENABLE}_!EN") (pintype "input"))
      (node (ref "R21") (pin "2") (pinfunction "2_2") (pintype "passive"))
      (node (ref "U5") (pin "45") (pinfunction "PA6_AD6_45") (pintype "bidirectional"))
    )
    (net (code "60") (name "5V") (class "Default")
      (node (ref "C10") (pin "1") (pinfunction "1_1") (pintype "passive"))
      (node (ref "C3") (pin "1") (pinfunction "1_1") (pintype "passive"))
      (node (ref "C6") (pin "2") (pinfunction "2_2") (pintype "passive"))
      (node (ref "C7") (pin "2") (pinfunction "2_2") (pintype "passive"))
      (node (ref "C8") (pin "1") (pinfunction "1_1") (pintype "passive"))
      (node (ref "J8") (pin "2") (pinfunction "2_2") (pintype "passive"))
      (node (ref "JP4") (pin "3") (pinfunction "3_3") (pintype "passive"))
      (node (ref "JP5") (pin "5") (pinfunction "5_5") (pintype "passive"))
      (node (ref "JP6") (pin "3") (pinfunction "3_3") (pintype "passive"))
      (node (ref "L1") (pin "2") (pinfunction "2_2") (pintype "passive"))
      (node (ref "P1") (pin "VDD") (pinfunction "VDD_VDD") (pintype "power_in"))
      (node (ref "P2") (pin "VDD") (pinfunction "VDD_VDD") (pintype "power_in"))
      (node (ref "P3") (pin "VDD") (pinfunction "VDD_VDD") (pintype "power_in"))
      (node (ref "P4") (pin "VDD") (pinfunction "VDD_VDD") (pintype "power_in"))
      (node (ref "R1") (pin "2") (pinfunction "2_2") (pintype "passive"))
      (node (ref "R12") (pin "2") (pinfunction "2_2") (pintype "passive"))
      (node (ref "R13") (pin "2") (pinfunction "2_2") (pintype "passive"))
      (node (ref "R16") (pin "2") (pinfunction "2_2") (pintype "passive"))
      (node (ref "R17") (pin "2") (pinfunction "2_2") (pintype "passive"))
      (node (ref "R19") (pin "1") (pinfunction "1_1") (pintype "passive"))
      (node (ref "R20") (pin "1") (pinfunction "1_1") (pintype "passive"))
      (node (ref "R21") (pin "1") (pinfunction "1_1") (pintype "passive"))
      (node (ref "R22") (pin "1") (pinfunction "1_1") (pintype "passive"))
      (node (ref "R4") (pin "1") (pinfunction "1_1") (pintype "passive"))
      (node (ref "SJ1") (pin "2") (pinfunction "2_2") (pintype "passive"))
      (node (ref "SJ10") (pin "2") (pinfunction "2_2") (pintype "passive"))
      (node (ref "SJ12") (pin "2") (pinfunction "2_2") (pintype "passive"))
      (node (ref "SJ13") (pin "2") (pinfunction "2_2") (pintype "passive"))
      (node (ref "SJ14") (pin "2") (pinfunction "2_2") (pintype "passive"))
      (node (ref "SJ15") (pin "2") (pinfunction "2_2") (pintype "passive"))
      (node (ref "SJ2") (pin "2") (pinfunction "2_2") (pintype "passive"))
      (node (ref "SJ3") (pin "2") (pinfunction "2_2") (pintype "passive"))
      (node (ref "SJ4") (pin "2") (pinfunction "2_2") (pintype "passive"))
      (node (ref "SJ5") (pin "2") (pinfunction "2_2") (pintype "passive"))
      (node (ref "SJ7") (pin "2") (pinfunction "2_2") (pintype "passive"))
      (node (ref "SJ8") (pin "2") (pinfunction "2_2") (pintype "passive"))
      (node (ref "SJ9") (pin "2") (pinfunction "2_2") (pintype "passive"))
      (node (ref "U3") (pin "1") (pinfunction "IN_1") (pintype "power_in"))
      (node (ref "U4") (pin "14") (pinfunction "VCCB_14") (pintype "power_in"))
      (node (ref "U5") (pin "21") (pinfunction "VCC_21") (pintype "power_in"))
      (node (ref "U5") (pin "52") (pinfunction "VCC_52") (pintype "power_in"))
      (node (ref "U5") (pin "62") (pinfunction "AREF_62") (pintype "power_in"))
      (node (ref "U5") (pin "64") (pinfunction "AVCC_64") (pintype "power_in"))
    )
    (net (code "61") (name "12V") (class "Default")
      (node (ref "C1") (pin "1") (pinfunction "1_1") (pintype "passive"))
      (node (ref "C17") (pin "+") (pinfunction "+_+") (pintype "passive"))
      (node (ref "C18") (pin "+") (pinfunction "+_+") (pintype "passive"))
      (node (ref "C19") (pin "+") (pinfunction "+_+") (pintype "passive"))
      (node (ref "C2") (pin "+") (pinfunction "+_+") (pintype "passive"))
      (node (ref "C20") (pin "+") (pinfunction "+_+") (pintype "passive"))
      (node (ref "F2") (pin "P$3") (pinfunction "P$3_P$3") (pintype "passive"))
      (node (ref "F2") (pin "P$4") (pinfunction "P$4_P$4") (pintype "passive"))
      (node (ref "J1") (pin "1") (pinfunction "1_1") (pintype "passive"))
      (node (ref "J4") (pin "1") (pinfunction "1_1") (pintype "passive"))
      (node (ref "J7") (pin "3") (pinfunction "3_3") (pintype "power_in"))
      (node (ref "J7") (pin "4") (pinfunction "4_4") (pintype "power_in"))
      (node (ref "J8") (pin "3") (pinfunction "3_3") (pintype "passive"))
      (node (ref "J9") (pin "3") (pinfunction "3_3") (pintype "power_in"))
      (node (ref "J9") (pin "4") (pinfunction "4_4") (pintype "power_in"))
      (node (ref "JP4") (pin "1") (pinfunction "1_1") (pintype "passive"))
      (node (ref "JP6") (pin "1") (pinfunction "1_1") (pintype "passive"))
      (node (ref "P1") (pin "VMOT") (pinfunction "VMOT_VMOT") (pintype "power_in"))
      (node (ref "P2") (pin "VMOT") (pinfunction "VMOT_VMOT") (pintype "power_in"))
      (node (ref "P3") (pin "VMOT") (pinfunction "VMOT_VMOT") (pintype "power_in"))
      (node (ref "P4") (pin "VMOT") (pinfunction "VMOT_VMOT") (pintype "power_in"))
      (node (ref "U1") (pin "4") (pinfunction "~{SHDN}_4") (pintype "input"))
      (node (ref "U1") (pin "5") (pinfunction "VIN_5") (pintype "power_in"))
    )
    (net (code "62") (name "GND") (class "Default")
      (node (ref "C1") (pin "2") (pinfunction "2_2") (pintype "passive"))
      (node (ref "C10") (pin "2") (pinfunction "2_2") (pintype "passive"))
      (node (ref "C11") (pin "2") (pinfunction "2_2") (pintype "passive"))
      (node (ref "C12") (pin "1") (pinfunction "1_1") (pintype "passive"))
      (node (ref "C13") (pin "1") (pinfunction "1_1") (pintype "passive"))
      (node (ref "C14") (pin "1") (pinfunction "1_1") (pintype "passive"))
      (node (ref "C15") (pin "1") (pinfunction "1_1") (pintype "passive"))
      (node (ref "C17") (pin "-") (pinfunction "-_-") (pintype "passive"))
      (node (ref "C18") (pin "-") (pinfunction "-_-") (pintype "passive"))
      (node (ref "C19") (pin "-") (pinfunction "-_-") (pintype "passive"))
      (node (ref "C2") (pin "-") (pinfunction "-_-") (pintype "passive"))
      (node (ref "C20") (pin "-") (pinfunction "-_-") (pintype "passive"))
      (node (ref "C3") (pin "2") (pinfunction "2_2") (pintype "passive"))
      (node (ref "C5") (pin "1") (pinfunction "1_1") (pintype "passive"))
      (node (ref "C6") (pin "1") (pinfunction "1_1") (pintype "passive"))
      (node (ref "C7") (pin "1") (pinfunction "1_1") (pintype "passive"))
      (node (ref "C8") (pin "2") (pinfunction "2_2") (pintype "passive"))
      (node (ref "C9") (pin "1") (pinfunction "1_1") (pintype "passive"))
      (node (ref "D1") (pin "A") (pinfunction "A_A") (pintype "passive"))
      (node (ref "D2") (pin "A") (pinfunction "A_A") (pintype "passive"))
      (node (ref "J1") (pin "2") (pinfunction "2_2") (pintype "passive"))
      (node (ref "J11") (pin "2") (pinfunction "2_2") (pintype "passive"))
      (node (ref "J12") (pin "2") (pinfunction "2_2") (pintype "passive"))
      (node (ref "J2") (pin "6") (pinfunction "GND_6") (pintype "power_in"))
      (node (ref "J2") (pin "C1") (pinfunction "SHEILD_C1") (pintype "bidirectional"))
      (node (ref "J2") (pin "C2") (pinfunction "SHIELD_C2") (pintype "bidirectional"))
      (node (ref "J2") (pin "C3") (pinfunction "SHIELD_C3") (pintype "bidirectional"))
      (node (ref "J2") (pin "C4") (pinfunction "SHIELD_C4") (pintype "bidirectional"))
      (node (ref "J2") (pin "CD1") (pinfunction "CD1_CD1") (pintype "bidirectional"))
      (node (ref "J3") (pin "GND") (pinfunction "GND_GND") (pintype "bidirectional"))
      (node (ref "J3") (pin "GND1") (pinfunction "GND_GND1") (pintype "bidirectional"))
      (node (ref "J3") (pin "GND2") (pinfunction "GND_GND2") (pintype "bidirectional"))
      (node (ref "J3") (pin "GND3") (pinfunction "GND_GND3") (pintype "bidirectional"))
      (node (ref "J3") (pin "GND4") (pinfunction "GND_GND4") (pintype "bidirectional"))
      (node (ref "J3") (pin "GND5") (pinfunction "GND_GND5") (pintype "bidirectional"))
      (node (ref "J3") (pin "GND6") (pinfunction "GND_GND6") (pintype "bidirectional"))
      (node (ref "J3") (pin "GND7") (pinfunction "GND_GND7") (pintype "bidirectional"))
      (node (ref "J3") (pin "GND8") (pinfunction "GND_GND8") (pintype "bidirectional"))
      (node (ref "J5") (pin "3") (pinfunction "3_3") (pintype "power_in"))
      (node (ref "J5") (pin "4") (pinfunction "4_4") (pintype "power_in"))
      (node (ref "J6") (pin "4") (pinfunction "S_4") (pintype "passive"))
      (node (ref "J6") (pin "5") (pinfunction "S_5") (pintype "passive"))
      (node (ref "J6") (pin "6") (pinfunction "S_6") (pintype "passive"))
      (node (ref "J8") (pin "1") (pinfunction "1_1") (pintype "passive"))
      (node (ref "JP10") (pin "3") (pinfunction "3_3") (pintype "passive"))
      (node (ref "JP3") (pin "2") (pinfunction "2_2") (pintype "passive"))
      (node (ref "JP5") (pin "1") (pinfunction "1_1") (pintype "passive"))
      (node (ref "JP7") (pin "3") (pinfunction "3_3") (pintype "passive"))
      (node (ref "JP8") (pin "3") (pinfunction "3_3") (pintype "passive"))
      (node (ref "JP9") (pin "3") (pinfunction "3_3") (pintype "passive"))
      (node (ref "LED1") (pin "C") (pinfunction "C_C") (pintype "passive"))
      (node (ref "P1") (pin "GNDMOT") (pinfunction "GNDMOT_GNDMOT") (pintype "power_in"))
      (node (ref "P1") (pin "GNDVDD") (pinfunction "GNDVDD_GNDVDD") (pintype "power_in"))
      (node (ref "P2") (pin "GNDMOT") (pinfunction "GNDMOT_GNDMOT") (pintype "power_in"))
      (node (ref "P2") (pin "GNDVDD") (pinfunction "GNDVDD_GNDVDD") (pintype "power_in"))
      (node (ref "P3") (pin "GNDMOT") (pinfunction "GNDMOT_GNDMOT") (pintype "power_in"))
      (node (ref "P3") (pin "GNDVDD") (pinfunction "GNDVDD_GNDVDD") (pintype "power_in"))
      (node (ref "P4") (pin "GNDMOT") (pinfunction "GNDMOT_GNDMOT") (pintype "power_in"))
      (node (ref "P4") (pin "GNDVDD") (pinfunction "GNDVDD_GNDVDD") (pintype "power_in"))
      (node (ref "Q1") (pin "2") (pinfunction "S_2") (pintype "passive"))
      (node (ref "Q2") (pin "1") (pinfunction "S1_1") (pintype "passive"))
      (node (ref "Q2") (pin "2") (pinfunction "S2_2") (pintype "passive"))
      (node (ref "Q2") (pin "3") (pinfunction "S3_3") (pintype "passive"))
      (node (ref "Q3") (pin "1") (pinfunction "S1_1") (pintype "passive"))
      (node (ref "Q3") (pin "2") (pinfunction "S2_2") (pintype "passive"))
      (node (ref "Q3") (pin "3") (pinfunction "S3_3") (pintype "passive"))
      (node (ref "Q5") (pin "2") (pinfunction "E_2") (pintype "passive"))
      (node (ref "R10") (pin "2") (pinfunction "2_2") (pintype "passive"))
      (node (ref "R2") (pin "2") (pinfunction "2_2") (pintype "passive"))
      (node (ref "R5") (pin "2") (pinfunction "2_2") (pintype "passive"))
      (node (ref "R8") (pin "2") (pinfunction "2_2") (pintype "passive"))
      (node (ref "S1") (pin "1") (pinfunction "1_1") (pintype "passive"))
      (node (ref "S1") (pin "2") (pinfunction "2_2") (pintype "passive"))
      (node (ref "SCREW1") (pin "GND") (pinfunction "P$1_GND") (pintype "bidirectional"))
      (node (ref "SCREW2") (pin "GND") (pinfunction "P$1_GND") (pintype "bidirectional"))
      (node (ref "SCREW3") (pin "GND") (pinfunction "P$1_GND") (pintype "bidirectional"))
      (node (ref "SCREW4") (pin "GND") (pinfunction "P$1_GND") (pintype "bidirectional"))
      (node (ref "U1") (pin "2") (pinfunction "GND_2") (pintype "power_in"))
      (node (ref "U2") (pin "2") (pinfunction "GND_2") (pintype "power_in"))
      (node (ref "U3") (pin "3") (pinfunction "GND_3") (pintype "power_in"))
      (node (ref "U4") (pin "7") (pinfunction "GND_7") (pintype "power_in"))
      (node (ref "U5") (pin "22") (pinfunction "GND_22") (pintype "power_in"))
      (node (ref "U5") (pin "53") (pinfunction "GND_53") (pintype "power_in"))
      (node (ref "U5") (pin "6") (pinfunction "UGND_6") (pintype "power_in"))
      (node (ref "U5") (pin "63") (pinfunction "AGND_63") (pintype "power_in"))
    )
    (net (code "63") (name "Net-(F1-PadP$2)") (class "Default")
      (node (ref "F1") (pin "P$2") (pinfunction "P$2_P$2") (pintype "passive"))
      (node (ref "J4") (pin "2") (pinfunction "2_2") (pintype "passive"))
    )
    (net (code "64") (name "Net-(J6A-S)") (class "Default")
      (node (ref "F2") (pin "P$1") (pinfunction "P$1_P$1") (pintype "passive"))
      (node (ref "F2") (pin "P$2") (pinfunction "P$2_P$2") (pintype "passive"))
      (node (ref "J5") (pin "1") (pinfunction "1_1") (pintype "power_in"))
      (node (ref "J5") (pin "2") (pinfunction "2_2") (pintype "power_in"))
      (node (ref "J6") (pin "1") (pinfunction "S_1") (pintype "passive"))
      (node (ref "J6") (pin "2") (pinfunction "S_2") (pintype "passive"))
      (node (ref "J6") (pin "3") (pinfunction "S_3") (pintype "passive"))
    )
    (net (code "65") (name "Net-(JP6-Pad2)") (class "Default")
      (node (ref "JP6") (pin "2") (pinfunction "2_2") (pintype "passive"))
      (node (ref "JP7") (pin "2") (pinfunction "2_2") (pintype "passive"))
    )
    (net (code "66") (name "Net-(JP10-Pad2)") (class "Default")
      (node (ref "JP10") (pin "2") (pinfunction "2_2") (pintype "passive"))
      (node (ref "JP4") (pin "2") (pinfunction "2_2") (pintype "passive"))
      (node (ref "JP8") (pin "2") (pinfunction "2_2") (pintype "passive"))
      (node (ref "JP9") (pin "2") (pinfunction "2_2") (pintype "passive"))
    )
    (net (code "67") (name "Net-(LED1-PadA)") (class "Default")
      (node (ref "LED1") (pin "A") (pinfunction "A_A") (pintype "passive"))
      (node (ref "R1") (pin "1") (pinfunction "1_1") (pintype "passive"))
    )
    (net (code "68") (name "Net-(P1-MOT-1A)") (class "Default")
      (node (ref "JP11") (pin "3") (pinfunction "3_3") (pintype "passive"))
      (node (ref "P1") (pin "1A") (pinfunction "MOT-1A_1A") (pintype "power_in"))
    )
    (net (code "69") (name "Net-(P1-MOT-1B)") (class "Default")
      (node (ref "JP11") (pin "4") (pinfunction "4_4") (pintype "passive"))
      (node (ref "P1") (pin "1B") (pinfunction "MOT-1B_1B") (pintype "power_in"))
    )
    (net (code "70") (name "Net-(P1-MOT-2A)") (class "Default")
      (node (ref "JP11") (pin "2") (pinfunction "2_2") (pintype "passive"))
      (node (ref "P1") (pin "2A") (pinfunction "MOT-2A_2A") (pintype "power_in"))
    )
    (net (code "71") (name "Net-(P1-MOT-2B)") (class "Default")
      (node (ref "JP11") (pin "1") (pinfunction "1_1") (pintype "passive"))
      (node (ref "P1") (pin "2B") (pinfunction "MOT-2B_2B") (pintype "power_in"))
    )
    (net (code "72") (name "Net-(P1-PadMS1)") (class "Default")
      (node (ref "P1") (pin "MS1") (pinfunction "MS1_MS1") (pintype "input"))
      (node (ref "SJ12") (pin "1") (pinfunction "1_1") (pintype "passive"))
    )
    (net (code "73") (name "Net-(P1-PadMS2)") (class "Default")
      (node (ref "P1") (pin "MS2") (pinfunction "MS2_MS2") (pintype "input"))
      (node (ref "SJ7") (pin "1") (pinfunction "1_1") (pintype "passive"))
    )
    (net (code "74") (name "Net-(P1-PadMS3)") (class "Default")
      (node (ref "P1") (pin "MS3") (pinfunction "MS3_MS3") (pintype "input"))
      (node (ref "SJ2") (pin "1") (pinfunction "1_1") (pintype "passive"))
    )
    (net (code "75") (name "Net-(P1-~{RESET})") (class "Default")
      (node (ref "P1") (pin "!RST") (pinfunction "~{RESET}_!RST") (pintype "input"))
      (node (ref "P1") (pin "!SLP") (pinfunction "~{SLEEP}_!SLP") (pintype "input"))
    )
    (net (code "76") (name "Net-(P2-MOT-1A)") (class "Default")
      (node (ref "JP12") (pin "3") (pinfunction "3_3") (pintype "passive"))
      (node (ref "P2") (pin "1A") (pinfunction "MOT-1A_1A") (pintype "power_in"))
    )
    (net (code "77") (name "Net-(P2-MOT-1B)") (class "Default")
      (node (ref "JP12") (pin "4") (pinfunction "4_4") (pintype "passive"))
      (node (ref "P2") (pin "1B") (pinfunction "MOT-1B_1B") (pintype "power_in"))
    )
    (net (code "78") (name "Net-(P2-MOT-2A)") (class "Default")
      (node (ref "JP12") (pin "2") (pinfunction "2_2") (pintype "passive"))
      (node (ref "P2") (pin "2A") (pinfunction "MOT-2A_2A") (pintype "power_in"))
    )
    (net (code "79") (name "Net-(P2-MOT-2B)") (class "Default")
      (node (ref "JP12") (pin "1") (pinfunction "1_1") (pintype "passive"))
      (node (ref "P2") (pin "2B") (pinfunction "MOT-2B_2B") (pintype "power_in"))
    )
    (net (code "80") (name "Net-(P2-PadMS1)") (class "Default")
      (node (ref "P2") (pin "MS1") (pinfunction "MS1_MS1") (pintype "input"))
      (node (ref "SJ13") (pin "1") (pinfunction "1_1") (pintype "passive"))
    )
    (net (code "81") (name "Net-(P2-PadMS2)") (class "Default")
      (node (ref "P2") (pin "MS2") (pinfunction "MS2_MS2") (pintype "input"))
      (node (ref "SJ8") (pin "1") (pinfunction "1_1") (pintype "passive"))
    )
    (net (code "82") (name "Net-(P2-PadMS3)") (class "Default")
      (node (ref "P2") (pin "MS3") (pinfunction "MS3_MS3") (pintype "input"))
      (node (ref "SJ3") (pin "1") (pinfunction "1_1") (pintype "passive"))
    )
    (net (code "83") (name "Net-(P2-~{RESET})") (class "Default")
      (node (ref "P2") (pin "!RST") (pinfunction "~{RESET}_!RST") (pintype "input"))
      (node (ref "P2") (pin "!SLP") (pinfunction "~{SLEEP}_!SLP") (pintype "input"))
    )
    (net (code "84") (name "Net-(P3-MOT-1A)") (class "Default")
      (node (ref "JP15") (pin "3") (pinfunction "3_3") (pintype "passive"))
      (node (ref "P3") (pin "1A") (pinfunction "MOT-1A_1A") (pintype "power_in"))
    )
    (net (code "85") (name "Net-(P3-MOT-1B)") (class "Default")
      (node (ref "JP15") (pin "4") (pinfunction "4_4") (pintype "passive"))
      (node (ref "P3") (pin "1B") (pinfunction "MOT-1B_1B") (pintype "power_in"))
    )
    (net (code "86") (name "Net-(P3-MOT-2A)") (class "Default")
      (node (ref "JP15") (pin "2") (pinfunction "2_2") (pintype "passive"))
      (node (ref "P3") (pin "2A") (pinfunction "MOT-2A_2A") (pintype "power_in"))
    )
    (net (code "87") (name "Net-(P3-MOT-2B)") (class "Default")
      (node (ref "JP15") (pin "1") (pinfunction "1_1") (pintype "passive"))
      (node (ref "P3") (pin "2B") (pinfunction "MOT-2B_2B") (pintype "power_in"))
    )
    (net (code "88") (name "Net-(P3-PadMS1)") (class "Default")
      (node (ref "P3") (pin "MS1") (pinfunction "MS1_MS1") (pintype "input"))
      (node (ref "SJ14") (pin "1") (pinfunction "1_1") (pintype "passive"))
    )
    (net (code "89") (name "Net-(P3-PadMS2)") (class "Default")
      (node (ref "P3") (pin "MS2") (pinfunction "MS2_MS2") (pintype "input"))
      (node (ref "SJ9") (pin "1") (pinfunction "1_1") (pintype "passive"))
    )
    (net (code "90") (name "Net-(P3-PadMS3)") (class "Default")
      (node (ref "P3") (pin "MS3") (pinfunction "MS3_MS3") (pintype "input"))
      (node (ref "SJ4") (pin "1") (pinfunction "1_1") (pintype "passive"))
    )
    (net (code "91") (name "Net-(P3-~{RESET})") (class "Default")
      (node (ref "P3") (pin "!RST") (pinfunction "~{RESET}_!RST") (pintype "input"))
      (node (ref "P3") (pin "!SLP") (pinfunction "~{SLEEP}_!SLP") (pintype "input"))
    )
    (net (code "92") (name "Net-(P4-MOT-1A)") (class "Default")
      (node (ref "JP13") (pin "3") (pinfunction "3_3") (pintype "passive"))
      (node (ref "P4") (pin "1A") (pinfunction "MOT-1A_1A") (pintype "power_in"))
    )
    (net (code "93") (name "Net-(P4-MOT-1B)") (class "Default")
      (node (ref "JP13") (pin "4") (pinfunction "4_4") (pintype "passive"))
      (node (ref "P4") (pin "1B") (pinfunction "MOT-1B_1B") (pintype "power_in"))
    )
    (net (code "94") (name "Net-(P4-MOT-2A)") (class "Default")
      (node (ref "JP13") (pin "2") (pinfunction "2_2") (pintype "passive"))
      (node (ref "P4") (pin "2A") (pinfunction "MOT-2A_2A") (pintype "power_in"))
    )
    (net (code "95") (name "Net-(P4-MOT-2B)") (class "Default")
      (node (ref "JP13") (pin "1") (pinfunction "1_1") (pintype "passive"))
      (node (ref "P4") (pin "2B") (pinfunction "MOT-2B_2B") (pintype "power_in"))
    )
    (net (code "96") (name "Net-(P4-PadMS1)") (class "Default")
      (node (ref "P4") (pin "MS1") (pinfunction "MS1_MS1") (pintype "input"))
      (node (ref "SJ15") (pin "1") (pinfunction "1_1") (pintype "passive"))
    )
    (net (code "97") (name "Net-(P4-PadMS2)") (class "Default")
      (node (ref "P4") (pin "MS2") (pinfunction "MS2_MS2") (pintype "input"))
      (node (ref "SJ10") (pin "1") (pinfunction "1_1") (pintype "passive"))
    )
    (net (code "98") (name "Net-(P4-PadMS3)") (class "Default")
      (node (ref "P4") (pin "MS3") (pinfunction "MS3_MS3") (pintype "input"))
      (node (ref "SJ5") (pin "1") (pinfunction "1_1") (pintype "passive"))
    )
    (net (code "99") (name "Net-(P4-~{RESET})") (class "Default")
      (node (ref "P4") (pin "!RST") (pinfunction "~{RESET}_!RST") (pintype "input"))
      (node (ref "P4") (pin "!SLP") (pinfunction "~{SLEEP}_!SLP") (pintype "input"))
    )
    (net (code "100") (name "Net-(Q1-D)") (class "Default")
      (node (ref "D2") (pin "C") (pinfunction "C_C") (pintype "passive"))
      (node (ref "F1") (pin "P$1") (pinfunction "P$1_P$1") (pintype "passive"))
      (node (ref "Q1") (pin "3") (pinfunction "D_3") (pintype "passive"))
    )
    (net (code "101") (name "Net-(Q1-G)") (class "Default")
      (node (ref "Q1") (pin "1") (pinfunction "G_1") (pintype "passive"))
      (node (ref "R3") (pin "2") (pinfunction "2_2") (pintype "passive"))
    )
    (net (code "102") (name "Net-(Q2-D)") (class "Default")
      (node (ref "J7") (pin "1") (pinfunction "1_1") (pintype "power_in"))
      (node (ref "J7") (pin "2") (pinfunction "2_2") (pintype "power_in"))
      (node (ref "Q2") (pin "5-8") (pinfunction "D_5-8") (pintype "passive"))
    )
    (net (code "103") (name "Net-(Q2-G)") (class "Default")
      (node (ref "Q2") (pin "4") (pinfunction "G_4") (pintype "passive"))
      (node (ref "R9") (pin "2") (pinfunction "2_2") (pintype "passive"))
    )
    (net (code "104") (name "Net-(Q3-D)") (class "Default")
      (node (ref "J9") (pin "1") (pinfunction "1_1") (pintype "power_in"))
      (node (ref "J9") (pin "2") (pinfunction "2_2") (pintype "power_in"))
      (node (ref "Q3") (pin "5-8") (pinfunction "D_5-8") (pintype "passive"))
    )
    (net (code "105") (name "Net-(Q3-G)") (class "Default")
      (node (ref "Q3") (pin "4") (pinfunction "G_4") (pintype "passive"))
      (node (ref "R11") (pin "2") (pinfunction "2_2") (pintype "passive"))
    )
    (net (code "106") (name "Net-(Q5-B)") (class "Default")
      (node (ref "JP7") (pin "1") (pinfunction "1_1") (pintype "passive"))
      (node (ref "Q5") (pin "1") (pinfunction "B_1") (pintype "passive"))
    )
    (net (code "107") (name "Net-(U1-CB)") (class "Default")
      (node (ref "C4") (pin "2") (pinfunction "2_2") (pintype "passive"))
      (node (ref "U1") (pin "1") (pinfunction "CB_1") (pintype "passive"))
    )
    (net (code "108") (name "Net-(U1-FB)") (class "Default")
      (node (ref "R4") (pin "2") (pinfunction "2_2") (pintype "passive"))
      (node (ref "R5") (pin "1") (pinfunction "1_1") (pintype "passive"))
      (node (ref "U1") (pin "3") (pinfunction "FB_3") (pintype "passive"))
    )
    (net (code "109") (name "Net-(U1-SW)") (class "Default")
      (node (ref "C4") (pin "1") (pinfunction "1_1") (pintype "passive"))
      (node (ref "D1") (pin "C") (pinfunction "C_C") (pintype "passive"))
      (node (ref "L1") (pin "1") (pinfunction "1_1") (pintype "passive"))
      (node (ref "U1") (pin "6") (pinfunction "SW_6") (pintype "passive"))
    )
    (net (code "110") (name "Net-(U5-D+)") (class "Default")
      (node (ref "R7") (pin "2") (pinfunction "2_2") (pintype "passive"))
      (node (ref "U5") (pin "5") (pinfunction "D+_5") (pintype "bidirectional"))
    )
    (net (code "111") (name "Net-(U5-D-)") (class "Default")
      (node (ref "R6") (pin "2") (pinfunction "2_2") (pintype "passive"))
      (node (ref "U5") (pin "4") (pinfunction "D-_4") (pintype "bidirectional"))
    )
    (net (code "112") (name "Net-(U5-UCAP)") (class "Default")
      (node (ref "C9") (pin "2") (pinfunction "2_2") (pintype "passive"))
      (node (ref "U5") (pin "7") (pinfunction "UCAP_7") (pintype "power_in"))
    )
    (net (code "113") (name "unconnected-(J2-DAT1-Pad8)") (class "Default")
      (node (ref "J2") (pin "8") (pinfunction "DAT1_8") (pintype "bidirectional"))
    )
    (net (code "114") (name "unconnected-(J2-DAT2-Pad1)") (class "Default")
      (node (ref "J2") (pin "1") (pinfunction "DAT2_1") (pintype "bidirectional"))
    )
    (net (code "115") (name "unconnected-(U2-IO3-Pad4)") (class "Default")
      (node (ref "U2") (pin "4") (pinfunction "IO3_4") (pintype "bidirectional"))
    )
    (net (code "116") (name "unconnected-(U2-IO4-Pad6)") (class "Default")
      (node (ref "U2") (pin "6") (pinfunction "IO4_6") (pintype "bidirectional"))
    )
  )
)
